# DAC_GainOutputStage3.net
KiCad netlist of a schematic drawn in EAGLE
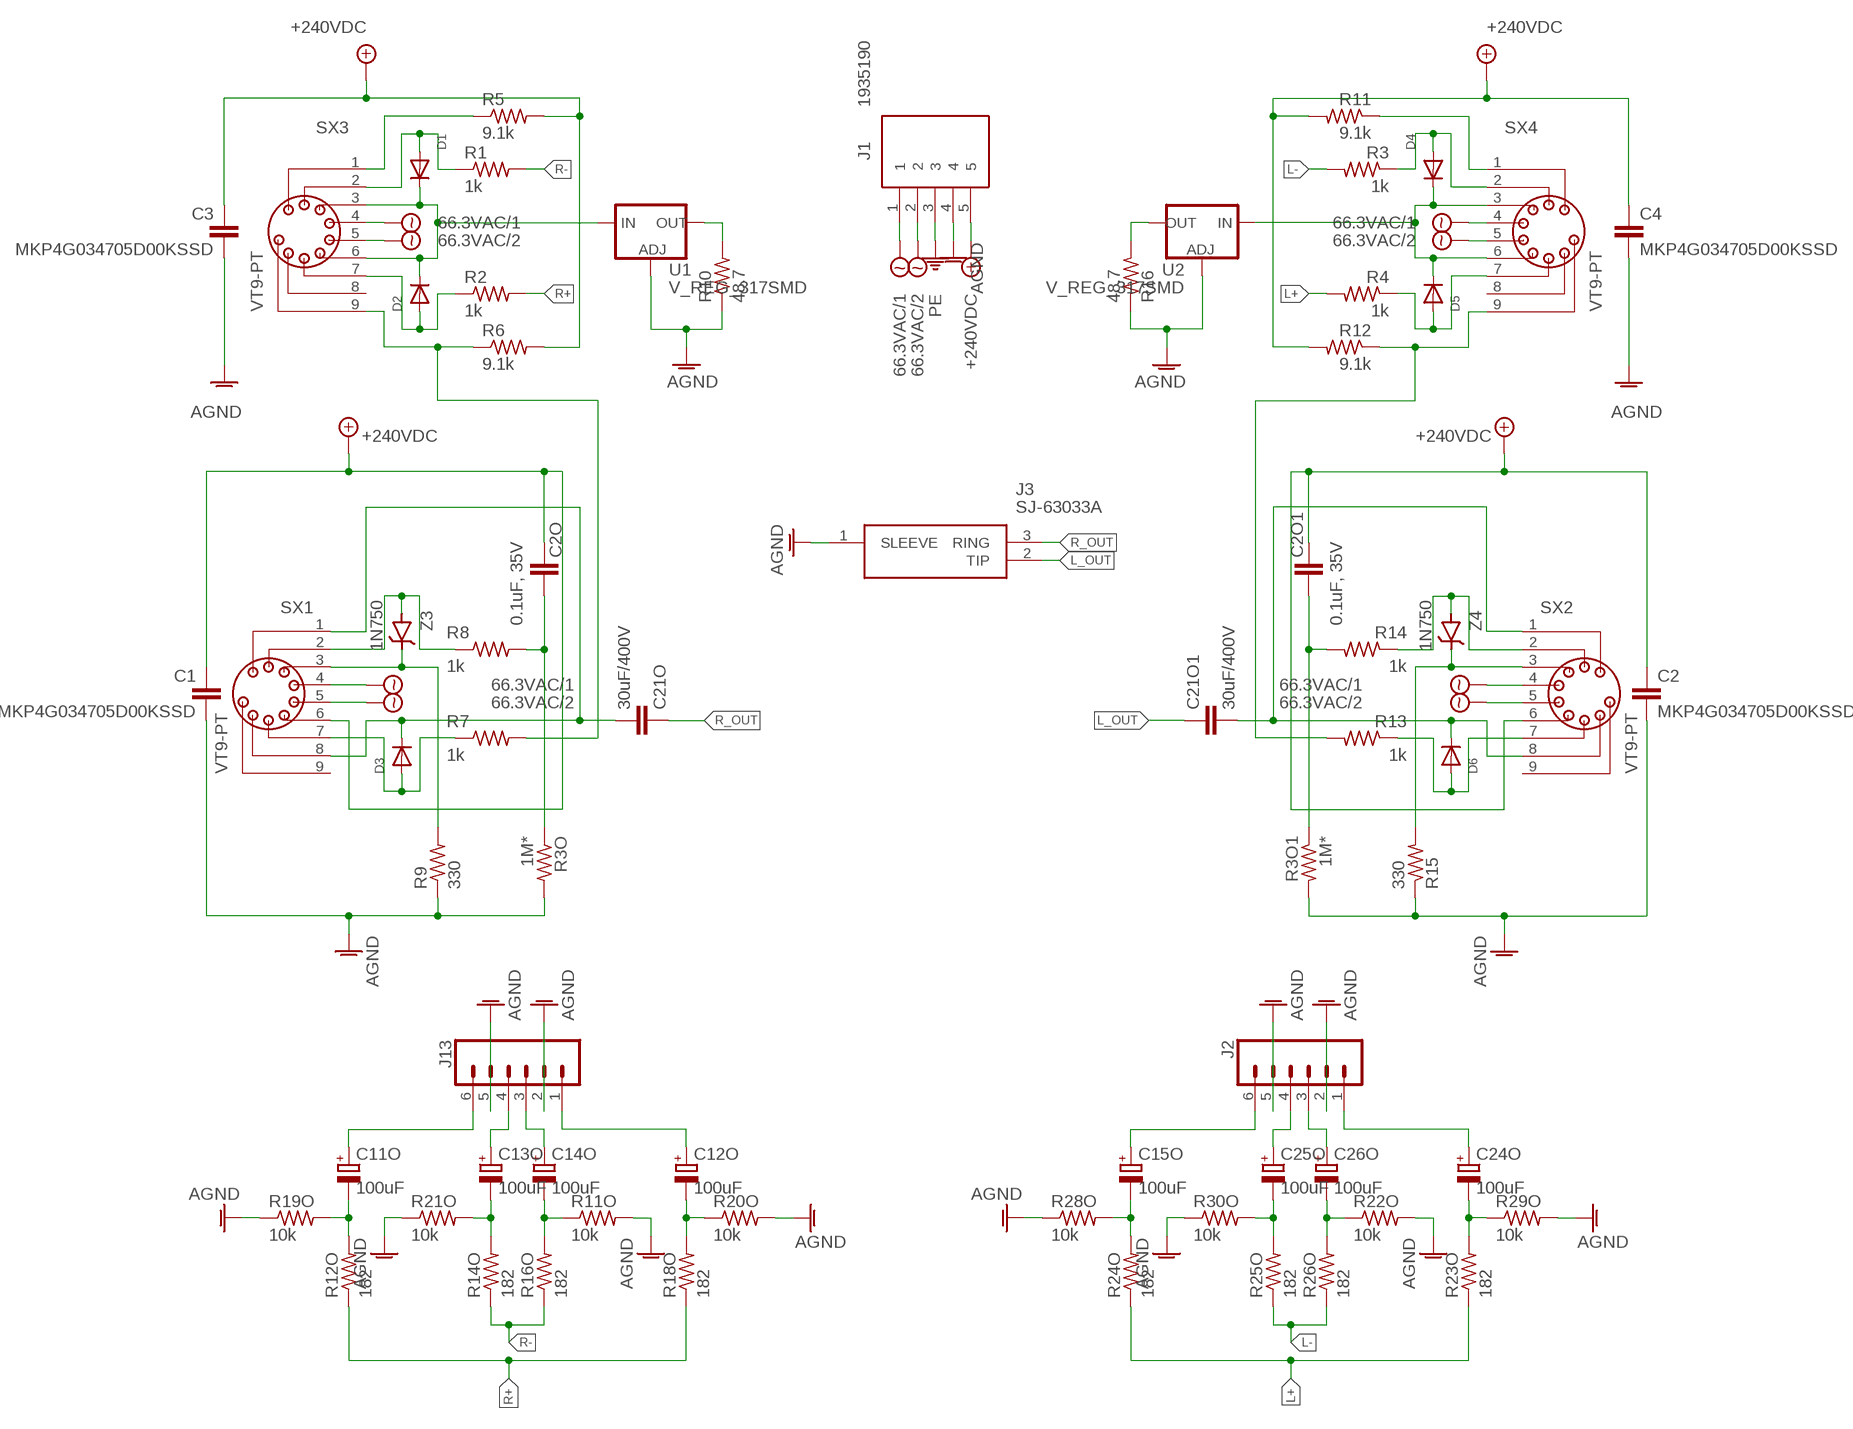
[diagram p0: schematic, sheet 1]

(export (version "E")
  (design (tool "Eeschema 10.0.6"))
  (components
    (comp (ref "C1")
      (value "MKP4G034705D00KSSD")
      (footprint "eagle-import:MKP4G034705D00KSSD")
      (fields (field (name "MOUSER_PART_NUMBER") "505-MKP4G034705DKSSD"))
      (libsource (lib "eagle-import") (part "MKP4G034705D00KSSD"))
    )
    (comp (ref "C2")
      (value "MKP4G034705D00KSSD")
      (footprint "eagle-import:MKP4G034705D00KSSD")
      (fields (field (name "MOUSER_PART_NUMBER") "505-MKP4G034705DKSSD"))
      (libsource (lib "eagle-import") (part "MKP4G034705D00KSSD"))
    )
    (comp (ref "C2O")
      (value "0.1uF, 35V")
      (footprint "eagle-import:MKS4B031002A00JC00")
      (fields
        (field (name "MANUFACTURER_PART_NUMBER") "MKS4B031002A00JC00")
        (field (name "MOUSER_PART_NUMBER") "505-MKS4B0312AJC")
      )
      (libsource (lib "eagle-import") (part "MKS4B031002A00JC00"))
    )
    (comp (ref "C2O1")
      (value "0.1uF, 35V")
      (footprint "eagle-import:MKS4B031002A00JC00")
      (fields
        (field (name "MANUFACTURER_PART_NUMBER") "MKS4B031002A00JC00")
        (field (name "MOUSER_PART_NUMBER") "505-MKS4B0312AJC")
      )
      (libsource (lib "eagle-import") (part "MKS4B031002A00JC00"))
    )
    (comp (ref "C3")
      (value "MKP4G034705D00KSSD")
      (footprint "eagle-import:MKP4G034705D00KSSD")
      (fields (field (name "MOUSER_PART_NUMBER") "505-MKP4G034705DKSSD"))
      (libsource (lib "eagle-import") (part "MKP4G034705D00KSSD"))
    )
    (comp (ref "C4")
      (value "MKP4G034705D00KSSD")
      (footprint "eagle-import:MKP4G034705D00KSSD")
      (fields (field (name "MOUSER_PART_NUMBER") "505-MKP4G034705DKSSD"))
      (libsource (lib "eagle-import") (part "MKP4G034705D00KSSD"))
    )
    (comp (ref "C11O")
      (value "100uF")
      (footprint "eagle-import:CAPPRD350W60D825H1300")
      (fields
        (field (name "ARROW_PART_NUMBER") "UFW1H101MPD1TD")
        (field (name "MOUSER_PART_NUMBER") "647-UFW1H101MPD1TD")
      )
      (libsource (lib "eagle-import") (part "UFW1H101MPD1TD"))
    )
    (comp (ref "C12O")
      (value "100uF")
      (footprint "eagle-import:CAPPRD350W60D825H1300")
      (fields
        (field (name "ARROW_PART_NUMBER") "UFW1H101MPD1TD")
        (field (name "MOUSER_PART_NUMBER") "647-UFW1H101MPD1TD")
      )
      (libsource (lib "eagle-import") (part "UFW1H101MPD1TD"))
    )
    (comp (ref "C13O")
      (value "100uF")
      (footprint "eagle-import:CAPPRD350W60D825H1300")
      (fields
        (field (name "ARROW_PART_NUMBER") "UFW1H101MPD1TD")
        (field (name "MOUSER_PART_NUMBER") "647-UFW1H101MPD1TD")
      )
      (libsource (lib "eagle-import") (part "UFW1H101MPD1TD"))
    )
    (comp (ref "C14O")
      (value "100uF")
      (footprint "eagle-import:CAPPRD350W60D825H1300")
      (fields
        (field (name "ARROW_PART_NUMBER") "UFW1H101MPD1TD")
        (field (name "MOUSER_PART_NUMBER") "647-UFW1H101MPD1TD")
      )
      (libsource (lib "eagle-import") (part "UFW1H101MPD1TD"))
    )
    (comp (ref "C15O")
      (value "100uF")
      (footprint "eagle-import:CAPPRD350W60D825H1300")
      (fields
        (field (name "ARROW_PART_NUMBER") "UFW1H101MPD1TD")
        (field (name "MOUSER_PART_NUMBER") "647-UFW1H101MPD1TD")
      )
      (libsource (lib "eagle-import") (part "UFW1H101MPD1TD"))
    )
    (comp (ref "C21O")
      (value "30uF/400V")
      (footprint "eagle-import:DCP4G053006ID2KSSD")
      (fields
        (field (name "MANUFACTURER_PART_NUMBER") "DCP4G053006ID2KSSD")
        (field (name "MOUSER_PART_NUMBER") "505-DCP4G0536ID2KSSD")
      )
      (libsource (lib "eagle-import") (part "DCP4G053006ID2KSSD"))
    )
    (comp (ref "C21O1")
      (value "30uF/400V")
      (footprint "eagle-import:DCP4G053006ID2KSSD")
      (fields
        (field (name "MANUFACTURER_PART_NUMBER") "DCP4G053006ID2KSSD")
        (field (name "MOUSER_PART_NUMBER") "505-DCP4G0536ID2KSSD")
      )
      (libsource (lib "eagle-import") (part "DCP4G053006ID2KSSD"))
    )
    (comp (ref "C24O")
      (value "100uF")
      (footprint "eagle-import:CAPPRD350W60D825H1300")
      (fields
        (field (name "ARROW_PART_NUMBER") "UFW1H101MPD1TD")
        (field (name "MOUSER_PART_NUMBER") "647-UFW1H101MPD1TD")
      )
      (libsource (lib "eagle-import") (part "UFW1H101MPD1TD"))
    )
    (comp (ref "C25O")
      (value "100uF")
      (footprint "eagle-import:CAPPRD350W60D825H1300")
      (fields
        (field (name "ARROW_PART_NUMBER") "UFW1H101MPD1TD")
        (field (name "MOUSER_PART_NUMBER") "647-UFW1H101MPD1TD")
      )
      (libsource (lib "eagle-import") (part "UFW1H101MPD1TD"))
    )
    (comp (ref "C26O")
      (value "100uF")
      (footprint "eagle-import:CAPPRD350W60D825H1300")
      (fields
        (field (name "ARROW_PART_NUMBER") "UFW1H101MPD1TD")
        (field (name "MOUSER_PART_NUMBER") "647-UFW1H101MPD1TD")
      )
      (libsource (lib "eagle-import") (part "UFW1H101MPD1TD"))
    )
    (comp (ref "D1")
      (value "DIODEDO-1N4148")
      (footprint "eagle-import:DO-1N4148")
      (libsource (lib "eagle-import") (part "DIODEDO-1N4148"))
    )
    (comp (ref "D2")
      (value "DIODEDO-1N4148")
      (footprint "eagle-import:DO-1N4148")
      (libsource (lib "eagle-import") (part "DIODEDO-1N4148"))
    )
    (comp (ref "D3")
      (value "DIODEDO-1N4148")
      (footprint "eagle-import:DO-1N4148")
      (libsource (lib "eagle-import") (part "DIODEDO-1N4148"))
    )
    (comp (ref "D4")
      (value "DIODEDO-1N4148")
      (footprint "eagle-import:DO-1N4148")
      (libsource (lib "eagle-import") (part "DIODEDO-1N4148"))
    )
    (comp (ref "D5")
      (value "DIODEDO-1N4148")
      (footprint "eagle-import:DO-1N4148")
      (libsource (lib "eagle-import") (part "DIODEDO-1N4148"))
    )
    (comp (ref "D6")
      (value "DIODEDO-1N4148")
      (footprint "eagle-import:DO-1N4148")
      (libsource (lib "eagle-import") (part "DIODEDO-1N4148"))
    )
    (comp (ref "J1")
      (value "1935190")
      (footprint "eagle-import:1935190")
      (fields (field (name "MOUSER_PART_NUMBER") "651-1935190"))
      (libsource (lib "eagle-import") (part "1935190"))
    )
    (comp (ref "J2")
      (value "CONN_06SILK_FEMALE_PTH")
      (footprint "eagle-import:1X06")
      (libsource (lib "eagle-import") (part "CONN_06SILK_FEMALE_PTH"))
    )
    (comp (ref "J3")
      (value "SJ-63033A")
      (footprint "eagle-import:SJ63033A")
      (libsource (lib "eagle-import") (part "SJ-63033A"))
    )
    (comp (ref "J13")
      (value "CONN_06SILK_FEMALE_PTH")
      (footprint "eagle-import:1X06")
      (libsource (lib "eagle-import") (part "CONN_06SILK_FEMALE_PTH"))
    )
    (comp (ref "R1")
      (value "1k")
      (footprint "eagle-import:0207_10")
      (libsource (lib "eagle-import") (part "R-US_0207/10"))
    )
    (comp (ref "R2")
      (value "1k")
      (footprint "eagle-import:0207_10")
      (libsource (lib "eagle-import") (part "R-US_0207/10"))
    )
    (comp (ref "R3")
      (value "1k")
      (footprint "eagle-import:0207_10")
      (libsource (lib "eagle-import") (part "R-US_0207/10"))
    )
    (comp (ref "R3O")
      (value "1M*")
      (footprint "eagle-import:RESAD1540W60L620D230")
      (fields
        (field (name "MANUFACTURER_PART_NUMBER") "LR1F1M0")
        (field (name "MOUSER_PART_NUMBER") "279-LR1F1M0")
      )
      (libsource (lib "eagle-import") (part "LR1F1M0"))
    )
    (comp (ref "R3O1")
      (value "1M*")
      (footprint "eagle-import:RESAD1540W60L620D230")
      (fields
        (field (name "MANUFACTURER_PART_NUMBER") "LR1F1M0")
        (field (name "MOUSER_PART_NUMBER") "279-LR1F1M0")
      )
      (libsource (lib "eagle-import") (part "LR1F1M0"))
    )
    (comp (ref "R4")
      (value "1k")
      (footprint "eagle-import:0207_10")
      (libsource (lib "eagle-import") (part "R-US_0207/10"))
    )
    (comp (ref "R5")
      (value "9.1k")
      (footprint "eagle-import:0207_10")
      (libsource (lib "eagle-import") (part "R-US_0207/10"))
    )
    (comp (ref "R6")
      (value "9.1k")
      (footprint "eagle-import:0207_10")
      (libsource (lib "eagle-import") (part "R-US_0207/10"))
    )
    (comp (ref "R7")
      (value "1k")
      (footprint "eagle-import:0207_10")
      (libsource (lib "eagle-import") (part "R-US_0207/10"))
    )
    (comp (ref "R8")
      (value "1k")
      (footprint "eagle-import:0207_10")
      (libsource (lib "eagle-import") (part "R-US_0207/10"))
    )
    (comp (ref "R9")
      (value "330")
      (footprint "eagle-import:0207_10")
      (libsource (lib "eagle-import") (part "R-US_0207/10"))
    )
    (comp (ref "R10")
      (value "48.7")
      (footprint "eagle-import:0207_10")
      (libsource (lib "eagle-import") (part "R-US_0207/10"))
    )
    (comp (ref "R11")
      (value "9.1k")
      (footprint "eagle-import:0207_10")
      (libsource (lib "eagle-import") (part "R-US_0207/10"))
    )
    (comp (ref "R11O")
      (value "10k")
      (footprint "eagle-import:RESAD1540W55L620D230")
      (fields
        (field (name "MANUFACTURER_PART_NUMBER") "LR1F10K")
        (field (name "MOUSER_PART_NUMBER") "279-LR1F10K")
      )
      (libsource (lib "eagle-import") (part "LR1F10K"))
    )
    (comp (ref "R12")
      (value "9.1k")
      (footprint "eagle-import:0207_10")
      (libsource (lib "eagle-import") (part "R-US_0207/10"))
    )
    (comp (ref "R12O")
      (value "182")
      (footprint "eagle-import:RESAD1590W60L630D240")
      (fields (field (name "MANUFACTURER_PART_NUMBER") "MF0207FTE52-182R"))
      (libsource (lib "eagle-import") (part "MF0207FTE52-182R"))
    )
    (comp (ref "R13")
      (value "1k")
      (footprint "eagle-import:0207_10")
      (libsource (lib "eagle-import") (part "R-US_0207/10"))
    )
    (comp (ref "R14")
      (value "1k")
      (footprint "eagle-import:0207_10")
      (libsource (lib "eagle-import") (part "R-US_0207/10"))
    )
    (comp (ref "R14O")
      (value "182")
      (footprint "eagle-import:RESAD1590W60L630D240")
      (fields (field (name "MANUFACTURER_PART_NUMBER") "MF0207FTE52-182R"))
      (libsource (lib "eagle-import") (part "MF0207FTE52-182R"))
    )
    (comp (ref "R15")
      (value "330")
      (footprint "eagle-import:0207_10")
      (libsource (lib "eagle-import") (part "R-US_0207/10"))
    )
    (comp (ref "R16")
      (value "48.7")
      (footprint "eagle-import:0207_10")
      (libsource (lib "eagle-import") (part "R-US_0207/10"))
    )
    (comp (ref "R16O")
      (value "182")
      (footprint "eagle-import:RESAD1590W60L630D240")
      (fields (field (name "MANUFACTURER_PART_NUMBER") "MF0207FTE52-182R"))
      (libsource (lib "eagle-import") (part "MF0207FTE52-182R"))
    )
    (comp (ref "R18O")
      (value "182")
      (footprint "eagle-import:RESAD1590W60L630D240")
      (fields (field (name "MANUFACTURER_PART_NUMBER") "MF0207FTE52-182R"))
      (libsource (lib "eagle-import") (part "MF0207FTE52-182R"))
    )
    (comp (ref "R19O")
      (value "10k")
      (footprint "eagle-import:RESAD1540W55L620D230")
      (fields
        (field (name "MANUFACTURER_PART_NUMBER") "LR1F10K")
        (field (name "MOUSER_PART_NUMBER") "279-LR1F10K")
      )
      (libsource (lib "eagle-import") (part "LR1F10K"))
    )
    (comp (ref "R20O")
      (value "10k")
      (footprint "eagle-import:RESAD1540W55L620D230")
      (fields
        (field (name "MANUFACTURER_PART_NUMBER") "LR1F10K")
        (field (name "MOUSER_PART_NUMBER") "279-LR1F10K")
      )
      (libsource (lib "eagle-import") (part "LR1F10K"))
    )
    (comp (ref "R21O")
      (value "10k")
      (footprint "eagle-import:RESAD1540W55L620D230")
      (fields
        (field (name "MANUFACTURER_PART_NUMBER") "LR1F10K")
        (field (name "MOUSER_PART_NUMBER") "279-LR1F10K")
      )
      (libsource (lib "eagle-import") (part "LR1F10K"))
    )
    (comp (ref "R22O")
      (value "10k")
      (footprint "eagle-import:RESAD1540W55L620D230")
      (fields
        (field (name "MANUFACTURER_PART_NUMBER") "LR1F10K")
        (field (name "MOUSER_PART_NUMBER") "279-LR1F10K")
      )
      (libsource (lib "eagle-import") (part "LR1F10K"))
    )
    (comp (ref "R23O")
      (value "182")
      (footprint "eagle-import:RESAD1590W60L630D240")
      (fields (field (name "MANUFACTURER_PART_NUMBER") "MF0207FTE52-182R"))
      (libsource (lib "eagle-import") (part "MF0207FTE52-182R"))
    )
    (comp (ref "R24O")
      (value "182")
      (footprint "eagle-import:RESAD1590W60L630D240")
      (fields (field (name "MANUFACTURER_PART_NUMBER") "MF0207FTE52-182R"))
      (libsource (lib "eagle-import") (part "MF0207FTE52-182R"))
    )
    (comp (ref "R25O")
      (value "182")
      (footprint "eagle-import:RESAD1590W60L630D240")
      (fields (field (name "MANUFACTURER_PART_NUMBER") "MF0207FTE52-182R"))
      (libsource (lib "eagle-import") (part "MF0207FTE52-182R"))
    )
    (comp (ref "R26O")
      (value "182")
      (footprint "eagle-import:RESAD1590W60L630D240")
      (fields (field (name "MANUFACTURER_PART_NUMBER") "MF0207FTE52-182R"))
      (libsource (lib "eagle-import") (part "MF0207FTE52-182R"))
    )
    (comp (ref "R28O")
      (value "10k")
      (footprint "eagle-import:RESAD1540W55L620D230")
      (fields
        (field (name "MANUFACTURER_PART_NUMBER") "LR1F10K")
        (field (name "MOUSER_PART_NUMBER") "279-LR1F10K")
      )
      (libsource (lib "eagle-import") (part "LR1F10K"))
    )
    (comp (ref "R29O")
      (value "10k")
      (footprint "eagle-import:RESAD1540W55L620D230")
      (fields
        (field (name "MANUFACTURER_PART_NUMBER") "LR1F10K")
        (field (name "MOUSER_PART_NUMBER") "279-LR1F10K")
      )
      (libsource (lib "eagle-import") (part "LR1F10K"))
    )
    (comp (ref "R30O")
      (value "10k")
      (footprint "eagle-import:RESAD1540W55L620D230")
      (fields
        (field (name "MANUFACTURER_PART_NUMBER") "LR1F10K")
        (field (name "MOUSER_PART_NUMBER") "279-LR1F10K")
      )
      (libsource (lib "eagle-import") (part "LR1F10K"))
    )
    (comp (ref "SX1")
      (value "VT9-PT")
      (footprint "eagle-import:VT9-PT")
      (libsource (lib "eagle-import") (part "VT9-PT"))
    )
    (comp (ref "SX2")
      (value "VT9-PT")
      (footprint "eagle-import:VT9-PT")
      (libsource (lib "eagle-import") (part "VT9-PT"))
    )
    (comp (ref "SX3")
      (value "VT9-PT")
      (footprint "eagle-import:VT9-PT")
      (libsource (lib "eagle-import") (part "VT9-PT"))
    )
    (comp (ref "SX4")
      (value "VT9-PT")
      (footprint "eagle-import:VT9-PT")
      (libsource (lib "eagle-import") (part "VT9-PT"))
    )
    (comp (ref "U1")
      (value "V_REG_317SMD")
      (footprint "eagle-import:SOT223")
      (libsource (lib "eagle-import") (part "V_REG_317SMD"))
    )
    (comp (ref "U2")
      (value "V_REG_317SMD")
      (footprint "eagle-import:SOT223")
      (libsource (lib "eagle-import") (part "V_REG_317SMD"))
    )
    (comp (ref "Z3")
      (value "1N750")
      (footprint "eagle-import:DIOAD1256W56L444D203")
      (fields (field (name "MOUSER_PART_NUMBER") "494-1N750(DO-35)"))
      (libsource (lib "eagle-import") (part "1N750"))
    )
    (comp (ref "Z4")
      (value "1N750")
      (footprint "eagle-import:DIOAD1256W56L444D203")
      (fields (field (name "MOUSER_PART_NUMBER") "494-1N750(DO-35)"))
      (libsource (lib "eagle-import") (part "1N750"))
    )
  )
  (nets
    (net (code "1") (name "+240VDC") (class "Default")
      (node (ref "C1") (pin "1") (pinfunction "1_1") (pintype "passive"))
      (node (ref "C2") (pin "1") (pinfunction "1_1") (pintype "passive"))
      (node (ref "C2O") (pin "1") (pinfunction "1_1") (pintype "passive"))
      (node (ref "C2O1") (pin "1") (pinfunction "1_1") (pintype "passive"))
      (node (ref "C3") (pin "1") (pinfunction "1_1") (pintype "passive"))
      (node (ref "C4") (pin "1") (pinfunction "1_1") (pintype "passive"))
      (node (ref "J1") (pin "5") (pinfunction "5_5") (pintype "bidirectional"))
      (node (ref "R11") (pin "2") (pinfunction "2_2") (pintype "passive"))
      (node (ref "R12") (pin "2") (pinfunction "2_2") (pintype "passive"))
      (node (ref "R5") (pin "2") (pinfunction "2_2") (pintype "passive"))
      (node (ref "R6") (pin "2") (pinfunction "2_2") (pintype "passive"))
      (node (ref "SX1") (pin "6") (pinfunction "6_6") (pintype "passive"))
      (node (ref "SX2") (pin "6") (pinfunction "6_6") (pintype "passive"))
    )
    (net (code "2") (name "66.3VAC{slash}1") (class "Default")
      (node (ref "J1") (pin "1") (pinfunction "1_1") (pintype "bidirectional"))
      (node (ref "SX1") (pin "4") (pinfunction "4_4") (pintype "passive"))
      (node (ref "SX2") (pin "4") (pinfunction "4_4") (pintype "passive"))
      (node (ref "SX3") (pin "4") (pinfunction "4_4") (pintype "passive"))
      (node (ref "SX4") (pin "4") (pinfunction "4_4") (pintype "passive"))
    )
    (net (code "3") (name "66.3VAC{slash}2") (class "Default")
      (node (ref "J1") (pin "2") (pinfunction "2_2") (pintype "bidirectional"))
      (node (ref "SX1") (pin "5") (pinfunction "5_5") (pintype "passive"))
      (node (ref "SX2") (pin "5") (pinfunction "5_5") (pintype "passive"))
      (node (ref "SX3") (pin "5") (pinfunction "5_5") (pintype "passive"))
      (node (ref "SX4") (pin "5") (pinfunction "5_5") (pintype "passive"))
    )
    (net (code "4") (name "AGND") (class "Default")
      (node (ref "C1") (pin "2") (pinfunction "2_2") (pintype "passive"))
      (node (ref "C2") (pin "2") (pinfunction "2_2") (pintype "passive"))
      (node (ref "C3") (pin "2") (pinfunction "2_2") (pintype "passive"))
      (node (ref "C4") (pin "2") (pinfunction "2_2") (pintype "passive"))
      (node (ref "J1") (pin "4") (pinfunction "4_4") (pintype "bidirectional"))
      (node (ref "J13") (pin "2") (pinfunction "2_2") (pintype "passive"))
      (node (ref "J13") (pin "5") (pinfunction "5_5") (pintype "passive"))
      (node (ref "J2") (pin "2") (pinfunction "2_2") (pintype "passive"))
      (node (ref "J2") (pin "5") (pinfunction "5_5") (pintype "passive"))
      (node (ref "J3") (pin "1") (pinfunction "SLEEVE_1") (pintype "bidirectional"))
      (node (ref "R10") (pin "1") (pinfunction "1_1") (pintype "passive"))
      (node (ref "R11O") (pin "2") (pinfunction "2_2") (pintype "passive"))
      (node (ref "R15") (pin "1") (pinfunction "1_1") (pintype "passive"))
      (node (ref "R16") (pin "1") (pinfunction "1_1") (pintype "passive"))
      (node (ref "R19O") (pin "1") (pinfunction "1_1") (pintype "passive"))
      (node (ref "R20O") (pin "2") (pinfunction "2_2") (pintype "passive"))
      (node (ref "R21O") (pin "1") (pinfunction "1_1") (pintype "passive"))
      (node (ref "R22O") (pin "2") (pinfunction "2_2") (pintype "passive"))
      (node (ref "R28O") (pin "1") (pinfunction "1_1") (pintype "passive"))
      (node (ref "R29O") (pin "2") (pinfunction "2_2") (pintype "passive"))
      (node (ref "R30O") (pin "1") (pinfunction "1_1") (pintype "passive"))
      (node (ref "R3O") (pin "2") (pinfunction "2_2") (pintype "passive"))
      (node (ref "R3O1") (pin "2") (pinfunction "2_2") (pintype "passive"))
      (node (ref "R9") (pin "1") (pinfunction "1_1") (pintype "passive"))
      (node (ref "U1") (pin "1") (pinfunction "ADJ_1") (pintype "input"))
      (node (ref "U2") (pin "1") (pinfunction "ADJ_1") (pintype "input"))
    )
    (net (code "5") (name "L+") (class "Default")
      (node (ref "R23O") (pin "1") (pinfunction "1_1") (pintype "passive"))
      (node (ref "R24O") (pin "1") (pinfunction "1_1") (pintype "passive"))
      (node (ref "R4") (pin "2") (pinfunction "2_2") (pintype "passive"))
    )
    (net (code "6") (name "L-") (class "Default")
      (node (ref "R25O") (pin "1") (pinfunction "1_1") (pintype "passive"))
      (node (ref "R26O") (pin "1") (pinfunction "1_1") (pintype "passive"))
      (node (ref "R3") (pin "2") (pinfunction "2_2") (pintype "passive"))
    )
    (net (code "7") (name "L_OUT") (class "Default")
      (node (ref "C21O1") (pin "1") (pinfunction "1_1") (pintype "passive"))
      (node (ref "J3") (pin "2") (pinfunction "TIP_2") (pintype "bidirectional"))
    )
    (net (code "8") (name "Net-(C2O-Pad2)") (class "Default")
      (node (ref "C2O") (pin "2") (pinfunction "2_2") (pintype "passive"))
      (node (ref "R3O") (pin "1") (pinfunction "1_1") (pintype "passive"))
      (node (ref "R8") (pin "2") (pinfunction "2_2") (pintype "passive"))
    )
    (net (code "9") (name "Net-(C2O1-Pad2)") (class "Default")
      (node (ref "C2O1") (pin "2") (pinfunction "2_2") (pintype "passive"))
      (node (ref "R14") (pin "2") (pinfunction "2_2") (pintype "passive"))
      (node (ref "R3O1") (pin "1") (pinfunction "1_1") (pintype "passive"))
    )
    (net (code "10") (name "Net-(C11O-+)") (class "Default")
      (node (ref "C11O") (pin "1") (pinfunction "+_1") (pintype "passive"))
      (node (ref "J13") (pin "6") (pinfunction "6_6") (pintype "passive"))
    )
    (net (code "11") (name "Net-(C11O--)") (class "Default")
      (node (ref "C11O") (pin "2") (pinfunction "-_2") (pintype "passive"))
      (node (ref "R12O") (pin "2") (pinfunction "2_2") (pintype "passive"))
      (node (ref "R19O") (pin "2") (pinfunction "2_2") (pintype "passive"))
    )
    (net (code "12") (name "Net-(C12O-+)") (class "Default")
      (node (ref "C12O") (pin "1") (pinfunction "+_1") (pintype "passive"))
      (node (ref "J13") (pin "1") (pinfunction "1_1") (pintype "passive"))
    )
    (net (code "13") (name "Net-(C12O--)") (class "Default")
      (node (ref "C12O") (pin "2") (pinfunction "-_2") (pintype "passive"))
      (node (ref "R18O") (pin "2") (pinfunction "2_2") (pintype "passive"))
      (node (ref "R20O") (pin "1") (pinfunction "1_1") (pintype "passive"))
    )
    (net (code "14") (name "Net-(C13O-+)") (class "Default")
      (node (ref "C13O") (pin "1") (pinfunction "+_1") (pintype "passive"))
      (node (ref "J13") (pin "4") (pinfunction "4_4") (pintype "passive"))
    )
    (net (code "15") (name "Net-(C13O--)") (class "Default")
      (node (ref "C13O") (pin "2") (pinfunction "-_2") (pintype "passive"))
      (node (ref "R14O") (pin "2") (pinfunction "2_2") (pintype "passive"))
      (node (ref "R21O") (pin "2") (pinfunction "2_2") (pintype "passive"))
    )
    (net (code "16") (name "Net-(C14O-+)") (class "Default")
      (node (ref "C14O") (pin "1") (pinfunction "+_1") (pintype "passive"))
      (node (ref "J13") (pin "3") (pinfunction "3_3") (pintype "passive"))
    )
    (net (code "17") (name "Net-(C14O--)") (class "Default")
      (node (ref "C14O") (pin "2") (pinfunction "-_2") (pintype "passive"))
      (node (ref "R11O") (pin "1") (pinfunction "1_1") (pintype "passive"))
      (node (ref "R16O") (pin "2") (pinfunction "2_2") (pintype "passive"))
    )
    (net (code "18") (name "Net-(C15O-+)") (class "Default")
      (node (ref "C15O") (pin "1") (pinfunction "+_1") (pintype "passive"))
      (node (ref "J2") (pin "6") (pinfunction "6_6") (pintype "passive"))
    )
    (net (code "19") (name "Net-(C15O--)") (class "Default")
      (node (ref "C15O") (pin "2") (pinfunction "-_2") (pintype "passive"))
      (node (ref "R24O") (pin "2") (pinfunction "2_2") (pintype "passive"))
      (node (ref "R28O") (pin "2") (pinfunction "2_2") (pintype "passive"))
    )
    (net (code "20") (name "Net-(C21O-Pad2)") (class "Default")
      (node (ref "C21O") (pin "2") (pinfunction "2_2") (pintype "passive"))
      (node (ref "D3") (pin "C") (pinfunction "C_C") (pintype "passive"))
      (node (ref "SX1") (pin "1") (pinfunction "1_1") (pintype "passive"))
      (node (ref "SX1") (pin "8") (pinfunction "8_8") (pintype "passive"))
    )
    (net (code "21") (name "Net-(C21O1-Pad2)") (class "Default")
      (node (ref "C21O1") (pin "2") (pinfunction "2_2") (pintype "passive"))
      (node (ref "D6") (pin "C") (pinfunction "C_C") (pintype "passive"))
      (node (ref "SX2") (pin "1") (pinfunction "1_1") (pintype "passive"))
      (node (ref "SX2") (pin "8") (pinfunction "8_8") (pintype "passive"))
    )
    (net (code "22") (name "Net-(C24O-+)") (class "Default")
      (node (ref "C24O") (pin "1") (pinfunction "+_1") (pintype "passive"))
      (node (ref "J2") (pin "1") (pinfunction "1_1") (pintype "passive"))
    )
    (net (code "23") (name "Net-(C24O--)") (class "Default")
      (node (ref "C24O") (pin "2") (pinfunction "-_2") (pintype "passive"))
      (node (ref "R23O") (pin "2") (pinfunction "2_2") (pintype "passive"))
      (node (ref "R29O") (pin "1") (pinfunction "1_1") (pintype "passive"))
    )
    (net (code "24") (name "Net-(C25O-+)") (class "Default")
      (node (ref "C25O") (pin "1") (pinfunction "+_1") (pintype "passive"))
      (node (ref "J2") (pin "4") (pinfunction "4_4") (pintype "passive"))
    )
    (net (code "25") (name "Net-(C25O--)") (class "Default")
      (node (ref "C25O") (pin "2") (pinfunction "-_2") (pintype "passive"))
      (node (ref "R25O") (pin "2") (pinfunction "2_2") (pintype "passive"))
      (node (ref "R30O") (pin "2") (pinfunction "2_2") (pintype "passive"))
    )
    (net (code "26") (name "Net-(C26O-+)") (class "Default")
      (node (ref "C26O") (pin "1") (pinfunction "+_1") (pintype "passive"))
      (node (ref "J2") (pin "3") (pinfunction "3_3") (pintype "passive"))
    )
    (net (code "27") (name "Net-(C26O--)") (class "Default")
      (node (ref "C26O") (pin "2") (pinfunction "-_2") (pintype "passive"))
      (node (ref "R22O") (pin "1") (pinfunction "1_1") (pintype "passive"))
      (node (ref "R26O") (pin "2") (pinfunction "2_2") (pintype "passive"))
    )
    (net (code "28") (name "Net-(D1-PadA)") (class "Default")
      (node (ref "D1") (pin "A") (pinfunction "A_A") (pintype "passive"))
      (node (ref "R1") (pin "1") (pinfunction "1_1") (pintype "passive"))
      (node (ref "SX3") (pin "2") (pinfunction "2_2") (pintype "passive"))
    )
    (net (code "29") (name "Net-(D2-PadA)") (class "Default")
      (node (ref "D2") (pin "A") (pinfunction "A_A") (pintype "passive"))
      (node (ref "R2") (pin "1") (pinfunction "1_1") (pintype "passive"))
      (node (ref "SX3") (pin "7") (pinfunction "7_7") (pintype "passive"))
    )
    (net (code "30") (name "Net-(D3-PadA)") (class "Default")
      (node (ref "D3") (pin "A") (pinfunction "A_A") (pintype "passive"))
      (node (ref "R7") (pin "1") (pinfunction "1_1") (pintype "passive"))
      (node (ref "SX1") (pin "7") (pinfunction "7_7") (pintype "passive"))
    )
    (net (code "31") (name "Net-(D4-PadA)") (class "Default")
      (node (ref "D4") (pin "A") (pinfunction "A_A") (pintype "passive"))
      (node (ref "R3") (pin "1") (pinfunction "1_1") (pintype "passive"))
      (node (ref "SX4") (pin "2") (pinfunction "2_2") (pintype "passive"))
    )
    (net (code "32") (name "Net-(D5-PadA)") (class "Default")
      (node (ref "D5") (pin "A") (pinfunction "A_A") (pintype "passive"))
      (node (ref "R4") (pin "1") (pinfunction "1_1") (pintype "passive"))
      (node (ref "SX4") (pin "7") (pinfunction "7_7") (pintype "passive"))
    )
    (net (code "33") (name "Net-(D6-PadA)") (class "Default")
      (node (ref "D6") (pin "A") (pinfunction "A_A") (pintype "passive"))
      (node (ref "R13") (pin "1") (pinfunction "1_1") (pintype "passive"))
      (node (ref "SX2") (pin "7") (pinfunction "7_7") (pintype "passive"))
    )
    (net (code "34") (name "Net-(R5-Pad1)") (class "Default")
      (node (ref "R5") (pin "1") (pinfunction "1_1") (pintype "passive"))
      (node (ref "SX3") (pin "1") (pinfunction "1_1") (pintype "passive"))
    )
    (net (code "35") (name "Net-(R6-Pad1)") (class "Default")
      (node (ref "R6") (pin "1") (pinfunction "1_1") (pintype "passive"))
      (node (ref "R7") (pin "2") (pinfunction "2_2") (pintype "passive"))
      (node (ref "SX3") (pin "9") (pinfunction "9_9") (pintype "passive"))
    )
    (net (code "36") (name "Net-(R11-Pad1)") (class "Default")
      (node (ref "R11") (pin "1") (pinfunction "1_1") (pintype "passive"))
      (node (ref "SX4") (pin "1") (pinfunction "1_1") (pintype "passive"))
    )
    (net (code "37") (name "Net-(R12-Pad1)") (class "Default")
      (node (ref "R12") (pin "1") (pinfunction "1_1") (pintype "passive"))
      (node (ref "R13") (pin "2") (pinfunction "2_2") (pintype "passive"))
      (node (ref "SX4") (pin "9") (pinfunction "9_9") (pintype "passive"))
    )
    (net (code "38") (name "Net-(U1-IN)") (class "Default")
      (node (ref "D1") (pin "C") (pinfunction "C_C") (pintype "passive"))
      (node (ref "D2") (pin "C") (pinfunction "C_C") (pintype "passive"))
      (node (ref "SX3") (pin "3") (pinfunction "3_3") (pintype "passive"))
      (node (ref "SX3") (pin "6") (pinfunction "6_6") (pintype "passive"))
      (node (ref "U1") (pin "3") (pinfunction "IN_3") (pintype "input"))
    )
    (net (code "39") (name "Net-(U1-OUT)") (class "Default")
      (node (ref "R10") (pin "2") (pinfunction "2_2") (pintype "passive"))
      (node (ref "U1") (pin "2") (pinfunction "OUT_2") (pintype "output"))
    )
    (net (code "40") (name "Net-(U2-IN)") (class "Default")
      (node (ref "D4") (pin "C") (pinfunction "C_C") (pintype "passive"))
      (node (ref "D5") (pin "C") (pinfunction "C_C") (pintype "passive"))
      (node (ref "SX4") (pin "3") (pinfunction "3_3") (pintype "passive"))
      (node (ref "SX4") (pin "6") (pinfunction "6_6") (pintype "passive"))
      (node (ref "U2") (pin "3") (pinfunction "IN_3") (pintype "input"))
    )
    (net (code "41") (name "Net-(U2-OUT)") (class "Default")
      (node (ref "R16") (pin "2") (pinfunction "2_2") (pintype "passive"))
      (node (ref "U2") (pin "2") (pinfunction "OUT_2") (pintype "output"))
    )
    (net (code "42") (name "Net-(Z3-A)") (class "Default")
      (node (ref "R8") (pin "1") (pinfunction "1_1") (pintype "passive"))
      (node (ref "SX1") (pin "2") (pinfunction "2_2") (pintype "passive"))
      (node (ref "Z3") (pin "2") (pinfunction "A_2") (pintype "passive"))
    )
    (net (code "43") (name "Net-(Z3-C)") (class "Default")
      (node (ref "R9") (pin "2") (pinfunction "2_2") (pintype "passive"))
      (node (ref "SX1") (pin "3") (pinfunction "3_3") (pintype "passive"))
      (node (ref "Z3") (pin "1") (pinfunction "C_1") (pintype "passive"))
    )
    (net (code "44") (name "Net-(Z4-A)") (class "Default")
      (node (ref "R14") (pin "1") (pinfunction "1_1") (pintype "passive"))
      (node (ref "SX2") (pin "2") (pinfunction "2_2") (pintype "passive"))
      (node (ref "Z4") (pin "2") (pinfunction "A_2") (pintype "passive"))
    )
    (net (code "45") (name "Net-(Z4-C)") (class "Default")
      (node (ref "R15") (pin "2") (pinfunction "2_2") (pintype "passive"))
      (node (ref "SX2") (pin "3") (pinfunction "3_3") (pintype "passive"))
      (node (ref "Z4") (pin "1") (pinfunction "C_1") (pintype "passive"))
    )
    (net (code "46") (name "PE") (class "Default")
      (node (ref "J1") (pin "3") (pinfunction "3_3") (pintype "bidirectional"))
    )
    (net (code "47") (name "R+") (class "Default")
      (node (ref "R12O") (pin "1") (pinfunction "1_1") (pintype "passive"))
      (node (ref "R18O") (pin "1") (pinfunction "1_1") (pintype "passive"))
      (node (ref "R2") (pin "2") (pinfunction "2_2") (pintype "passive"))
    )
    (net (code "48") (name "R-") (class "Default")
      (node (ref "R1") (pin "2") (pinfunction "2_2") (pintype "passive"))
      (node (ref "R14O") (pin "1") (pinfunction "1_1") (pintype "passive"))
      (node (ref "R16O") (pin "1") (pinfunction "1_1") (pintype "passive"))
    )
    (net (code "49") (name "R_OUT") (class "Default")
      (node (ref "C21O") (pin "1") (pinfunction "1_1") (pintype "passive"))
      (node (ref "J3") (pin "3") (pinfunction "RING_3") (pintype "bidirectional"))
    )
    (net (code "50") (name "unconnected-(SX1-Pad9)") (class "Default")
      (node (ref "SX1") (pin "9") (pinfunction "9_9") (pintype "passive"))
    )
    (net (code "51") (name "unconnected-(SX2-Pad9)") (class "Default")
      (node (ref "SX2") (pin "9") (pinfunction "9_9") (pintype "passive"))
    )
    (net (code "52") (name "unconnected-(SX3-Pad8)") (class "Default")
      (node (ref "SX3") (pin "8") (pinfunction "8_8") (pintype "passive"))
    )
    (net (code "53") (name "unconnected-(SX4-Pad8)") (class "Default")
      (node (ref "SX4") (pin "8") (pinfunction "8_8") (pintype "passive"))
    )
  )
)
